# ADC.net
KiCad netlist of a schematic drawn in Altium Designer
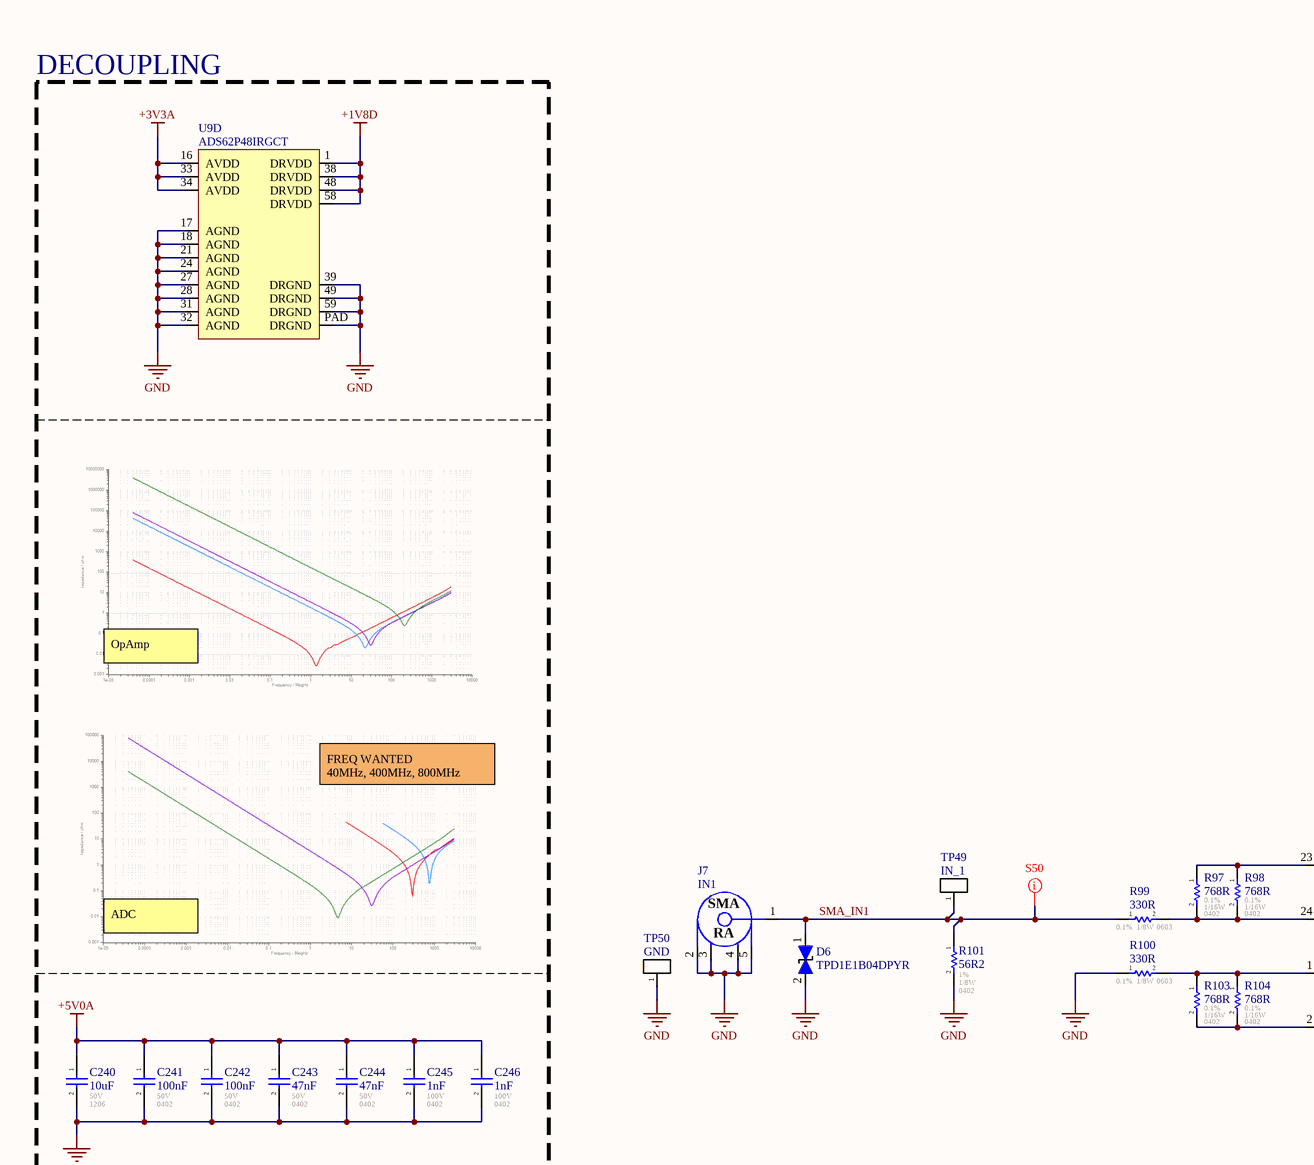
[diagram p0: ADC.SchDoc, top left]
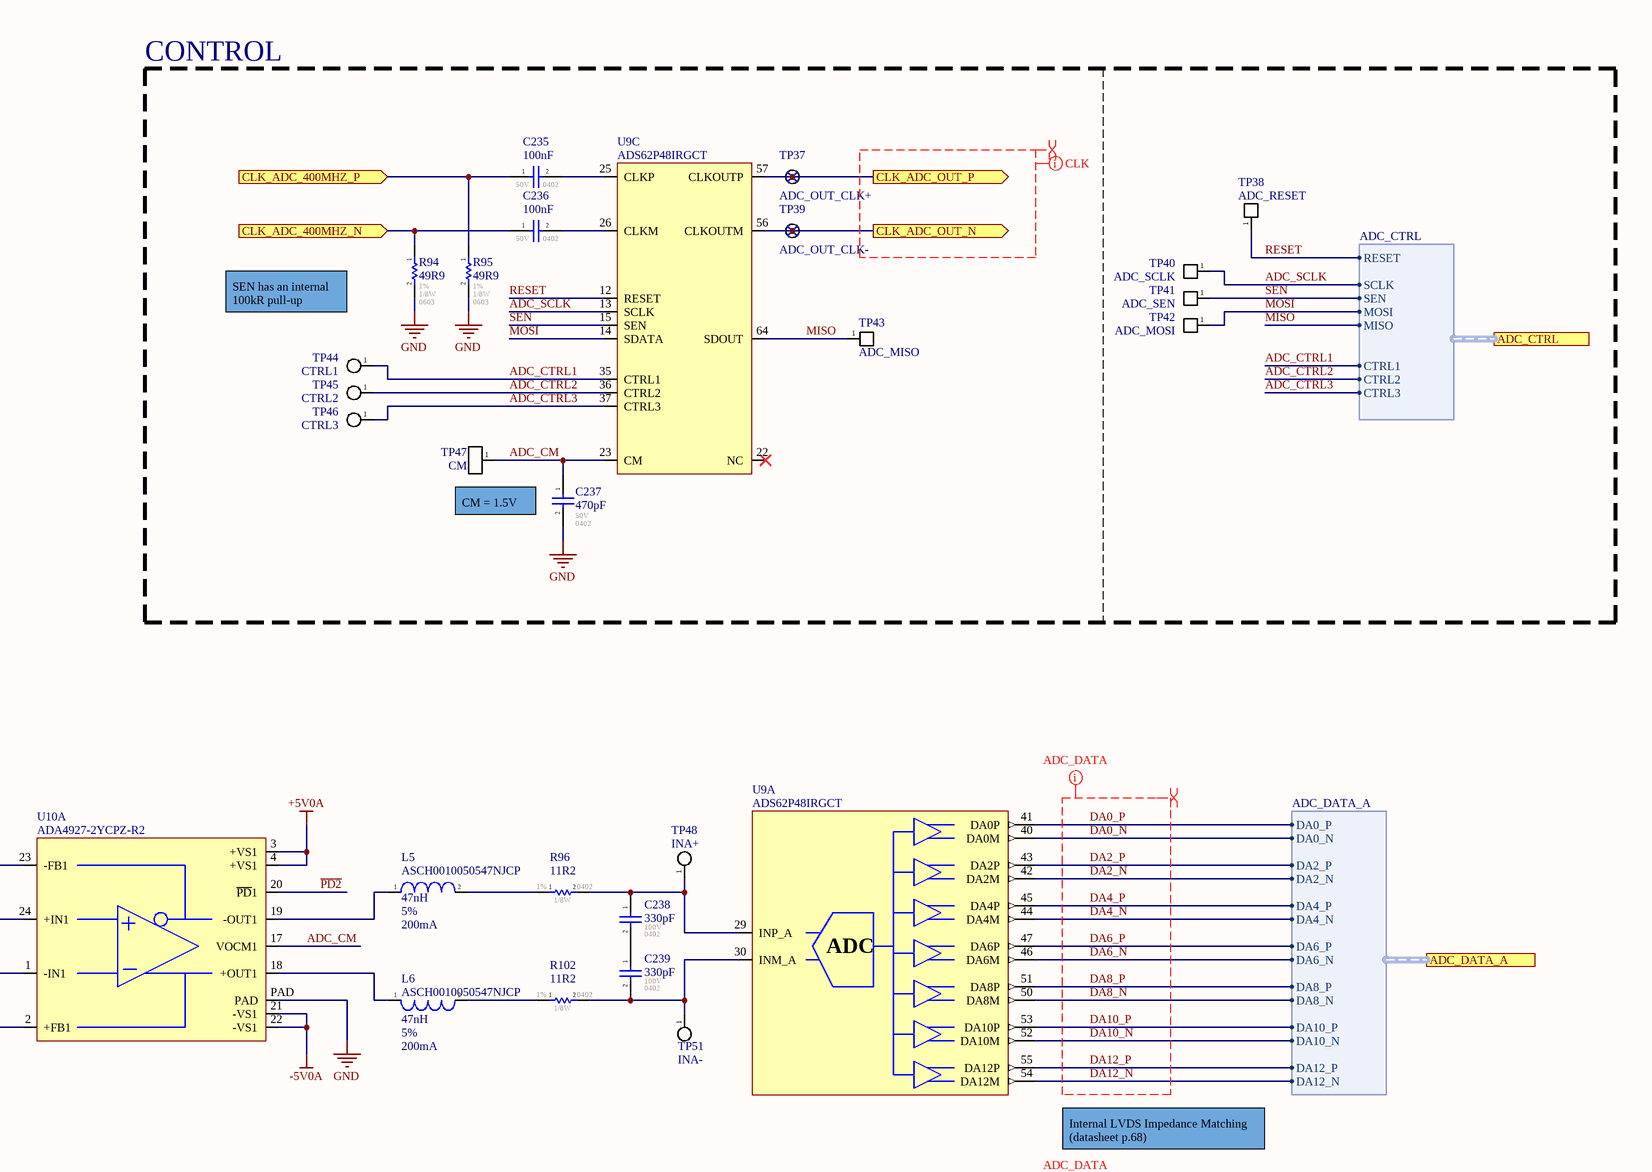
[diagram p1: ADC.SchDoc, top right]
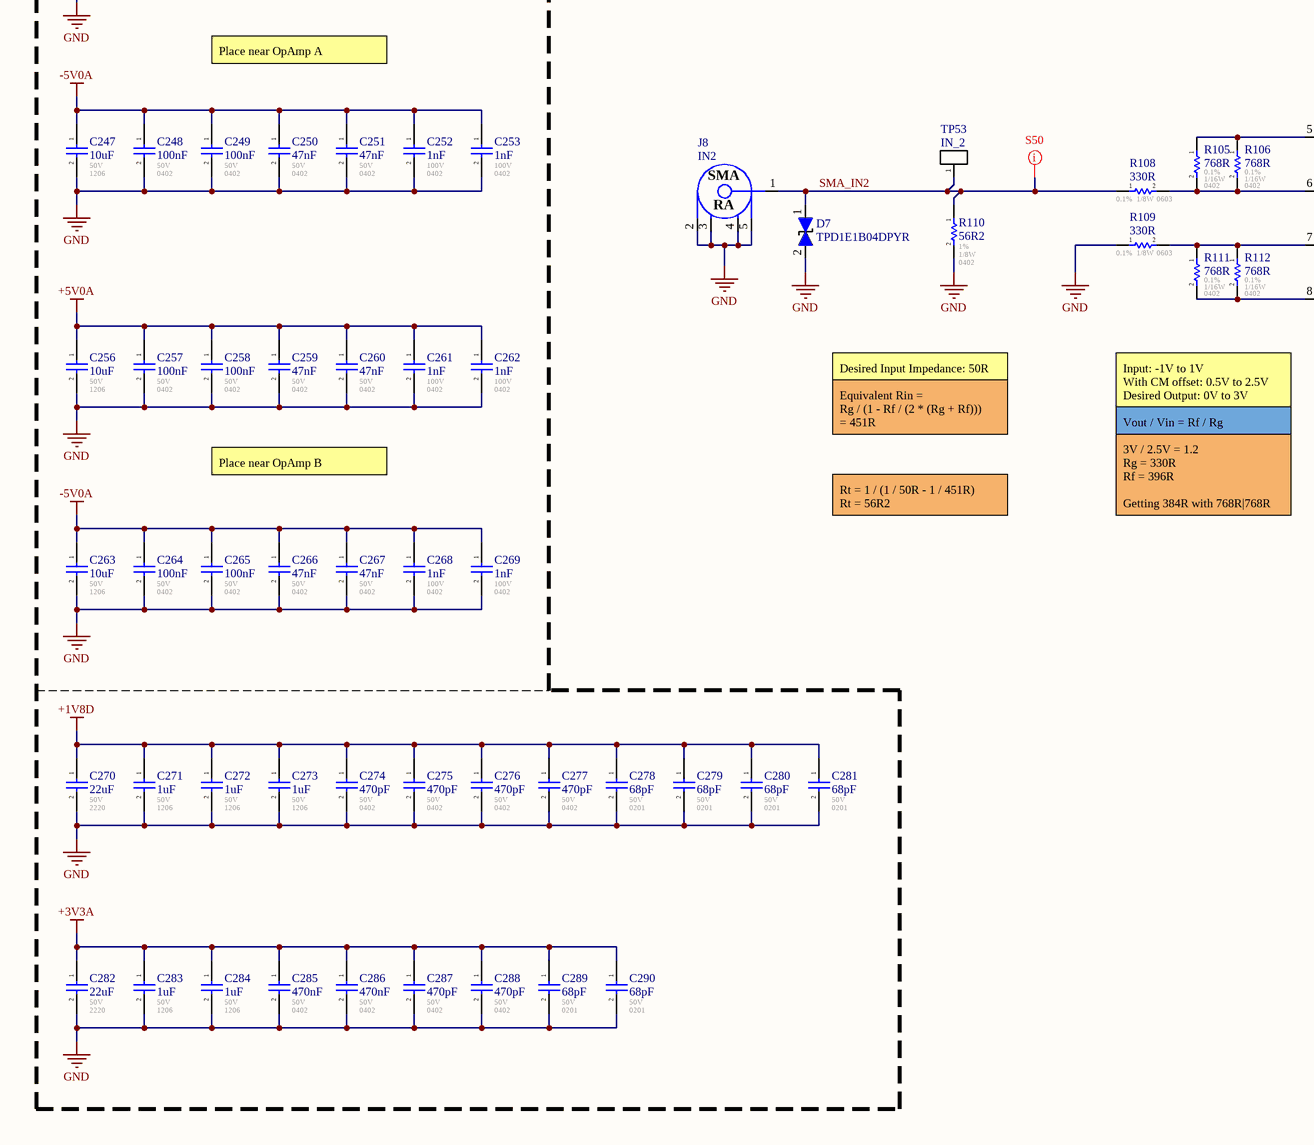
[diagram p2: ADC.SchDoc, bottom left]
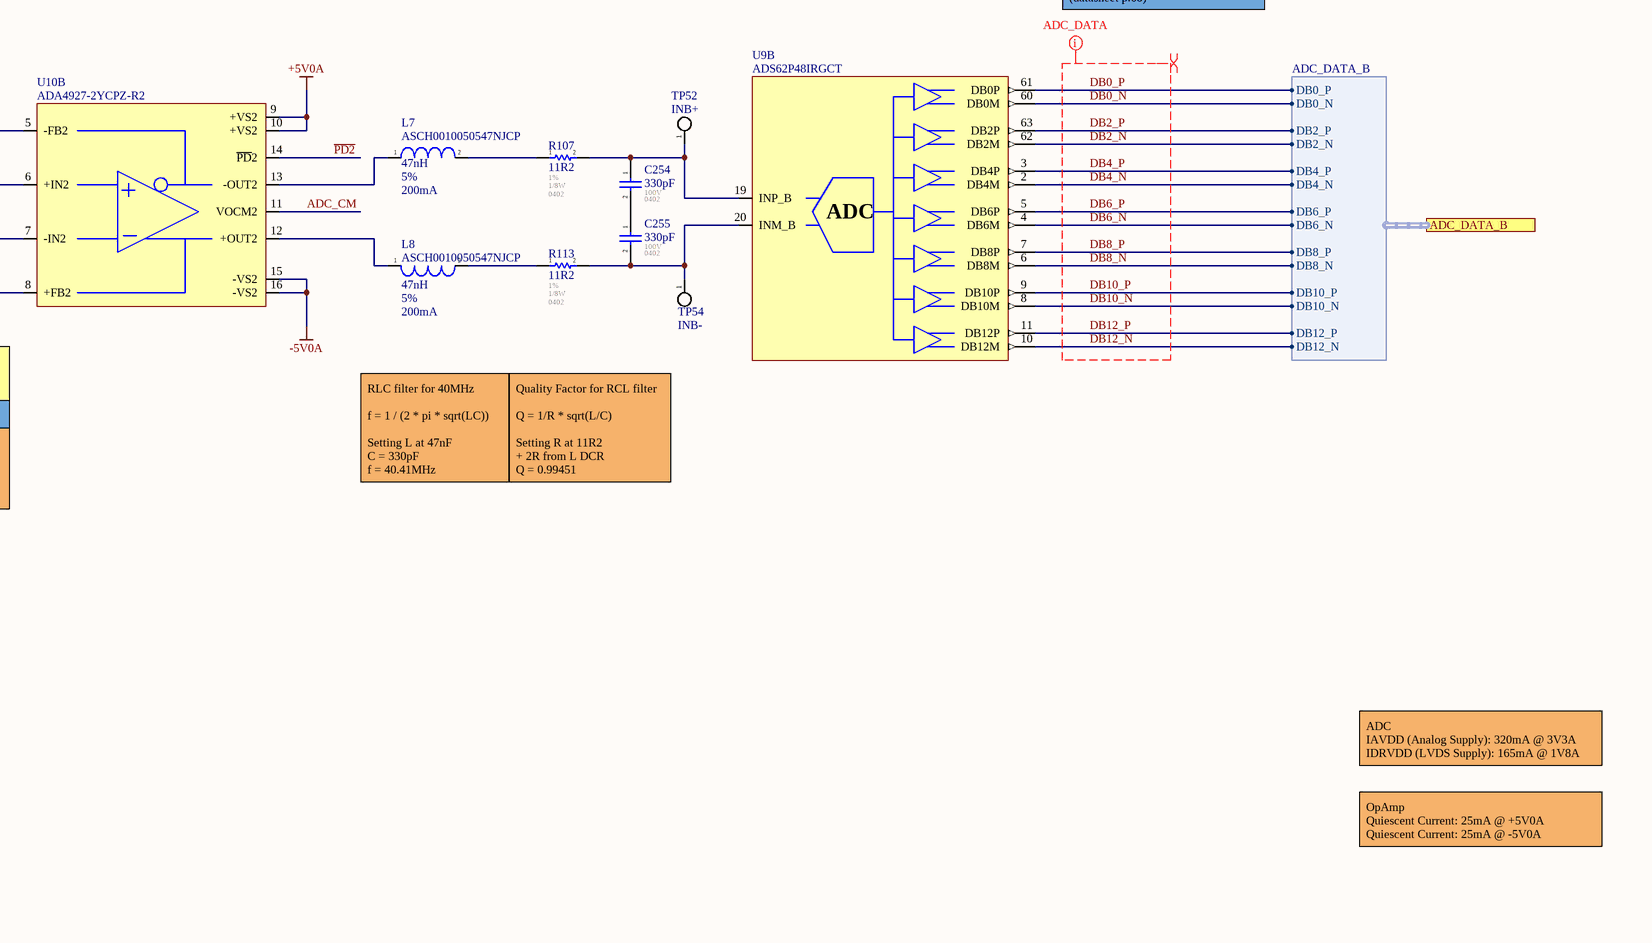
[diagram p3: ADC.SchDoc, bottom right]

(export (version "E")
  (design (tool "Eeschema 10.0.6"))
  (components
    (comp (ref "C235")
      (value "100nF")
      (footprint "0402")
      (description "GCM155R71H104KE02J\r\n0402 100nF 10% X7R Ceramic Capacitor")
      (fields
        (field (name "MFR") "Murata")
        (field (name "PART#") "GCM155R71H104KE02J")
        (field (name "VOLTAGE - RATED") "50V")
      )
      (libsource (lib "Symbols") (part "CAP_CER"))
    )
    (comp (ref "C236")
      (value "100nF")
      (footprint "0402")
      (description "GCM155R71H104KE02J\r\n0402 100nF 10% X7R Ceramic Capacitor")
      (fields
        (field (name "MFR") "Murata")
        (field (name "PART#") "GCM155R71H104KE02J")
        (field (name "VOLTAGE - RATED") "50V")
      )
      (libsource (lib "Symbols") (part "CAP_CER"))
    )
    (comp (ref "C237")
      (value "470pF")
      (footprint "0402")
      (description "GCM155R71H471KA37J\r\n0402 470pF 10% X7R Ceramic Capacitor")
      (fields
        (field (name "MFR") "Murata")
        (field (name "PART#") "GCM155R71H471KA37J")
        (field (name "VOLTAGE - RATED") "50V")
      )
      (libsource (lib "Symbols") (part "CAP_CER"))
    )
    (comp (ref "C238")
      (value "330pF")
      (footprint "0402")
      (description "GCM155R72A331KA37D\r\n0402 330pF 10% X7R Ceramic Capacitor")
      (fields
        (field (name "MFR") "Murata")
        (field (name "PART#") "GCM155R72A331KA37D")
        (field (name "VOLTAGE - RATED") "100V")
      )
      (libsource (lib "Symbols") (part "CAP_CER"))
    )
    (comp (ref "C239")
      (value "330pF")
      (footprint "0402")
      (description "GCM155R72A331KA37D\r\n0402 330pF 10% X7R Ceramic Capacitor")
      (fields
        (field (name "MFR") "Murata")
        (field (name "PART#") "GCM155R72A331KA37D")
        (field (name "VOLTAGE - RATED") "100V")
      )
      (libsource (lib "Symbols") (part "CAP_CER"))
    )
    (comp (ref "C240")
      (value "10uF")
      (footprint "1206")
      (description "GRT31CR61H106KE01L\r\n1206 10uF 10% X5R Ceramic Capacitor")
      (fields
        (field (name "MFR") "Murata")
        (field (name "VOLTAGE - RATED") "50V")
        (field (name "TOLERANCE") "10%")
      )
      (libsource (lib "Symbols") (part "CAP_CER"))
    )
    (comp (ref "C241")
      (value "100nF")
      (footprint "0402")
      (description "GCM155R71H104KE02J\r\n0402 100nF 10% X7R Ceramic Capacitor")
      (fields
        (field (name "MFR") "Murata")
        (field (name "PART#") "GCM155R71H104KE02J")
        (field (name "VOLTAGE - RATED") "50V")
      )
      (libsource (lib "Symbols") (part "CAP_CER"))
    )
    (comp (ref "C242")
      (value "100nF")
      (footprint "0402")
      (description "GCM155R71H104KE02J\r\n0402 100nF 10% X7R Ceramic Capacitor")
      (fields
        (field (name "MFR") "Murata")
        (field (name "PART#") "GCM155R71H104KE02J")
        (field (name "VOLTAGE - RATED") "50V")
      )
      (libsource (lib "Symbols") (part "CAP_CER"))
    )
    (comp (ref "C243")
      (value "47nF")
      (footprint "0402")
      (description "GCM155R71H473KE02J\r\n0402 47nF 10% X7R Ceramic Capacitor")
      (fields
        (field (name "MFR") "Murata")
        (field (name "PART#") "GCM155R71H473KE02J")
        (field (name "VOLTAGE - RATED") "50V")
      )
      (libsource (lib "Symbols") (part "CAP_CER"))
    )
    (comp (ref "C244")
      (value "47nF")
      (footprint "0402")
      (description "GCM155R71H473KE02J\r\n0402 47nF 10% X7R Ceramic Capacitor")
      (fields
        (field (name "MFR") "Murata")
        (field (name "PART#") "GCM155R71H473KE02J")
        (field (name "VOLTAGE - RATED") "50V")
      )
      (libsource (lib "Symbols") (part "CAP_CER"))
    )
    (comp (ref "C245")
      (value "1nF")
      (footprint "0402")
      (description "GCM155R72A102KA37D\r\n0402 1nF 10% X7R Ceramic Capacitor")
      (fields
        (field (name "MFR") "Murata")
        (field (name "PART#") "GCM155R72A102KA37D")
        (field (name "VOLTAGE - RATED") "100V")
      )
      (libsource (lib "Symbols") (part "CAP_CER"))
    )
    (comp (ref "C246")
      (value "1nF")
      (footprint "0402")
      (description "GCM155R72A102KA37D\r\n0402 1nF 10% X7R Ceramic Capacitor")
      (fields
        (field (name "MFR") "Murata")
        (field (name "PART#") "GCM155R72A102KA37D")
        (field (name "VOLTAGE - RATED") "100V")
      )
      (libsource (lib "Symbols") (part "CAP_CER"))
    )
    (comp (ref "C247")
      (value "10uF")
      (footprint "1206")
      (description "GRT31CR61H106KE01L\r\n1206 10uF 10% X5R Ceramic Capacitor")
      (fields
        (field (name "MFR") "Murata")
        (field (name "VOLTAGE - RATED") "50V")
        (field (name "TOLERANCE") "10%")
      )
      (libsource (lib "Symbols") (part "CAP_CER"))
    )
    (comp (ref "C248")
      (value "100nF")
      (footprint "0402")
      (description "GCM155R71H104KE02J\r\n0402 100nF 10% X7R Ceramic Capacitor")
      (fields
        (field (name "MFR") "Murata")
        (field (name "PART#") "GCM155R71H104KE02J")
        (field (name "VOLTAGE - RATED") "50V")
      )
      (libsource (lib "Symbols") (part "CAP_CER"))
    )
    (comp (ref "C249")
      (value "100nF")
      (footprint "0402")
      (description "GCM155R71H104KE02J\r\n0402 100nF 10% X7R Ceramic Capacitor")
      (fields
        (field (name "MFR") "Murata")
        (field (name "PART#") "GCM155R71H104KE02J")
        (field (name "VOLTAGE - RATED") "50V")
      )
      (libsource (lib "Symbols") (part "CAP_CER"))
    )
    (comp (ref "C250")
      (value "47nF")
      (footprint "0402")
      (description "GCM155R71H473KE02J\r\n0402 47nF 10% X7R Ceramic Capacitor")
      (fields
        (field (name "MFR") "Murata")
        (field (name "PART#") "GCM155R71H473KE02J")
        (field (name "VOLTAGE - RATED") "50V")
      )
      (libsource (lib "Symbols") (part "CAP_CER"))
    )
    (comp (ref "C251")
      (value "47nF")
      (footprint "0402")
      (description "GCM155R71H473KE02J\r\n0402 47nF 10% X7R Ceramic Capacitor")
      (fields
        (field (name "MFR") "Murata")
        (field (name "PART#") "GCM155R71H473KE02J")
        (field (name "VOLTAGE - RATED") "50V")
      )
      (libsource (lib "Symbols") (part "CAP_CER"))
    )
    (comp (ref "C252")
      (value "1nF")
      (footprint "0402")
      (description "GCM155R72A102KA37D\r\n0402 1nF 10% X7R Ceramic Capacitor")
      (fields
        (field (name "MFR") "Murata")
        (field (name "PART#") "GCM155R72A102KA37D")
        (field (name "VOLTAGE - RATED") "100V")
      )
      (libsource (lib "Symbols") (part "CAP_CER"))
    )
    (comp (ref "C253")
      (value "1nF")
      (footprint "0402")
      (description "GCM155R72A102KA37D\r\n0402 1nF 10% X7R Ceramic Capacitor")
      (fields
        (field (name "MFR") "Murata")
        (field (name "PART#") "GCM155R72A102KA37D")
        (field (name "VOLTAGE - RATED") "100V")
      )
      (libsource (lib "Symbols") (part "CAP_CER"))
    )
    (comp (ref "C254")
      (value "330pF")
      (footprint "0402")
      (description "GCM155R72A331KA37D\r\n0402 330pF 10% X7R Ceramic Capacitor")
      (fields
        (field (name "MFR") "Murata")
        (field (name "PART#") "GCM155R72A331KA37D")
        (field (name "VOLTAGE - RATED") "100V")
      )
      (libsource (lib "Symbols") (part "CAP_CER"))
    )
    (comp (ref "C255")
      (value "330pF")
      (footprint "0402")
      (description "GCM155R72A331KA37D\r\n0402 330pF 10% X7R Ceramic Capacitor")
      (fields
        (field (name "MFR") "Murata")
        (field (name "PART#") "GCM155R72A331KA37D")
        (field (name "VOLTAGE - RATED") "100V")
      )
      (libsource (lib "Symbols") (part "CAP_CER"))
    )
    (comp (ref "C256")
      (value "10uF")
      (footprint "1206")
      (description "GRT31CR61H106KE01L\r\n1206 10uF 10% X5R Ceramic Capacitor")
      (fields
        (field (name "MFR") "Murata")
        (field (name "VOLTAGE - RATED") "50V")
        (field (name "TOLERANCE") "10%")
      )
      (libsource (lib "Symbols") (part "CAP_CER"))
    )
    (comp (ref "C257")
      (value "100nF")
      (footprint "0402")
      (description "GCM155R71H104KE02J\r\n0402 100nF 10% X7R Ceramic Capacitor")
      (fields
        (field (name "MFR") "Murata")
        (field (name "PART#") "GCM155R71H104KE02J")
        (field (name "VOLTAGE - RATED") "50V")
      )
      (libsource (lib "Symbols") (part "CAP_CER"))
    )
    (comp (ref "C258")
      (value "100nF")
      (footprint "0402")
      (description "GCM155R71H104KE02J\r\n0402 100nF 10% X7R Ceramic Capacitor")
      (fields
        (field (name "MFR") "Murata")
        (field (name "PART#") "GCM155R71H104KE02J")
        (field (name "VOLTAGE - RATED") "50V")
      )
      (libsource (lib "Symbols") (part "CAP_CER"))
    )
    (comp (ref "C259")
      (value "47nF")
      (footprint "0402")
      (description "GCM155R71H473KE02J\r\n0402 47nF 10% X7R Ceramic Capacitor")
      (fields
        (field (name "MFR") "Murata")
        (field (name "PART#") "GCM155R71H473KE02J")
        (field (name "VOLTAGE - RATED") "50V")
      )
      (libsource (lib "Symbols") (part "CAP_CER"))
    )
    (comp (ref "C260")
      (value "47nF")
      (footprint "0402")
      (description "GCM155R71H473KE02J\r\n0402 47nF 10% X7R Ceramic Capacitor")
      (fields
        (field (name "MFR") "Murata")
        (field (name "PART#") "GCM155R71H473KE02J")
        (field (name "VOLTAGE - RATED") "50V")
      )
      (libsource (lib "Symbols") (part "CAP_CER"))
    )
    (comp (ref "C261")
      (value "1nF")
      (footprint "0402")
      (description "GCM155R72A102KA37D\r\n0402 1nF 10% X7R Ceramic Capacitor")
      (fields
        (field (name "MFR") "Murata")
        (field (name "PART#") "GCM155R72A102KA37D")
        (field (name "VOLTAGE - RATED") "100V")
      )
      (libsource (lib "Symbols") (part "CAP_CER"))
    )
    (comp (ref "C262")
      (value "1nF")
      (footprint "0402")
      (description "GCM155R72A102KA37D\r\n0402 1nF 10% X7R Ceramic Capacitor")
      (fields
        (field (name "MFR") "Murata")
        (field (name "PART#") "GCM155R72A102KA37D")
        (field (name "VOLTAGE - RATED") "100V")
      )
      (libsource (lib "Symbols") (part "CAP_CER"))
    )
    (comp (ref "C263")
      (value "10uF")
      (footprint "1206")
      (description "GRT31CR61H106KE01L\r\n1206 10uF 10% X5R Ceramic Capacitor")
      (fields
        (field (name "MFR") "Murata")
        (field (name "VOLTAGE - RATED") "50V")
        (field (name "TOLERANCE") "10%")
      )
      (libsource (lib "Symbols") (part "CAP_CER"))
    )
    (comp (ref "C264")
      (value "100nF")
      (footprint "0402")
      (description "GCM155R71H104KE02J\r\n0402 100nF 10% X7R Ceramic Capacitor")
      (fields
        (field (name "MFR") "Murata")
        (field (name "PART#") "GCM155R71H104KE02J")
        (field (name "VOLTAGE - RATED") "50V")
      )
      (libsource (lib "Symbols") (part "CAP_CER"))
    )
    (comp (ref "C265")
      (value "100nF")
      (footprint "0402")
      (description "GCM155R71H104KE02J\r\n0402 100nF 10% X7R Ceramic Capacitor")
      (fields
        (field (name "MFR") "Murata")
        (field (name "PART#") "GCM155R71H104KE02J")
        (field (name "VOLTAGE - RATED") "50V")
      )
      (libsource (lib "Symbols") (part "CAP_CER"))
    )
    (comp (ref "C266")
      (value "47nF")
      (footprint "0402")
      (description "GCM155R71H473KE02J\r\n0402 47nF 10% X7R Ceramic Capacitor")
      (fields
        (field (name "MFR") "Murata")
        (field (name "PART#") "GCM155R71H473KE02J")
        (field (name "VOLTAGE - RATED") "50V")
      )
      (libsource (lib "Symbols") (part "CAP_CER"))
    )
    (comp (ref "C267")
      (value "47nF")
      (footprint "0402")
      (description "GCM155R71H473KE02J\r\n0402 47nF 10% X7R Ceramic Capacitor")
      (fields
        (field (name "MFR") "Murata")
        (field (name "PART#") "GCM155R71H473KE02J")
        (field (name "VOLTAGE - RATED") "50V")
      )
      (libsource (lib "Symbols") (part "CAP_CER"))
    )
    (comp (ref "C268")
      (value "1nF")
      (footprint "0402")
      (description "GCM155R72A102KA37D\r\n0402 1nF 10% X7R Ceramic Capacitor")
      (fields
        (field (name "MFR") "Murata")
        (field (name "PART#") "GCM155R72A102KA37D")
        (field (name "VOLTAGE - RATED") "100V")
      )
      (libsource (lib "Symbols") (part "CAP_CER"))
    )
    (comp (ref "C269")
      (value "1nF")
      (footprint "0402")
      (description "GCM155R72A102KA37D\r\n0402 1nF 10% X7R Ceramic Capacitor")
      (fields
        (field (name "MFR") "Murata")
        (field (name "PART#") "GCM155R72A102KA37D")
        (field (name "VOLTAGE - RATED") "100V")
      )
      (libsource (lib "Symbols") (part "CAP_CER"))
    )
    (comp (ref "C270")
      (value "22uF")
      (footprint "2220")
      (description "CGA9P3X7R1H226M250KB\r\n2220 22uF 20% X7R Ceramic Capacitor")
      (fields
        (field (name "MFR") "TDK")
        (field (name "VOLTAGE - RATED") "50V")
        (field (name "TOLERANCE") "20%")
      )
      (libsource (lib "Symbols") (part "CAP_CER"))
    )
    (comp (ref "C271")
      (value "1uF")
      (footprint "1206")
      (description "GCJ31CR71H105KA12L\r\n1206 1uF 10% X7R Ceramic Capacitor")
      (fields
        (field (name "MFR") "Murata")
        (field (name "PART#") "GCJ31CR71H105KA12L")
        (field (name "VOLTAGE - RATED") "50V")
      )
      (libsource (lib "Symbols") (part "CAP_CER"))
    )
    (comp (ref "C272")
      (value "1uF")
      (footprint "1206")
      (description "GCJ31CR71H105KA12L\r\n1206 1uF 10% X7R Ceramic Capacitor")
      (fields
        (field (name "MFR") "Murata")
        (field (name "PART#") "GCJ31CR71H105KA12L")
        (field (name "VOLTAGE - RATED") "50V")
      )
      (libsource (lib "Symbols") (part "CAP_CER"))
    )
    (comp (ref "C273")
      (value "1uF")
      (footprint "1206")
      (description "GCJ31CR71H105KA12L\r\n1206 1uF 10% X7R Ceramic Capacitor")
      (fields
        (field (name "MFR") "Murata")
        (field (name "PART#") "GCJ31CR71H105KA12L")
        (field (name "VOLTAGE - RATED") "50V")
      )
      (libsource (lib "Symbols") (part "CAP_CER"))
    )
    (comp (ref "C274")
      (value "470pF")
      (footprint "0402")
      (description "GCM155R71H471KA37J\r\n0402 470pF 10% X7R Ceramic Capacitor")
      (fields
        (field (name "MFR") "Murata")
        (field (name "PART#") "GCM155R71H471KA37J")
        (field (name "VOLTAGE - RATED") "50V")
      )
      (libsource (lib "Symbols") (part "CAP_CER"))
    )
    (comp (ref "C275")
      (value "470pF")
      (footprint "0402")
      (description "GCM155R71H471KA37J\r\n0402 470pF 10% X7R Ceramic Capacitor")
      (fields
        (field (name "MFR") "Murata")
        (field (name "PART#") "GCM155R71H471KA37J")
        (field (name "VOLTAGE - RATED") "50V")
      )
      (libsource (lib "Symbols") (part "CAP_CER"))
    )
    (comp (ref "C276")
      (value "470pF")
      (footprint "0402")
      (description "GCM155R71H471KA37J\r\n0402 470pF 10% X7R Ceramic Capacitor")
      (fields
        (field (name "MFR") "Murata")
        (field (name "PART#") "GCM155R71H471KA37J")
        (field (name "VOLTAGE - RATED") "50V")
      )
      (libsource (lib "Symbols") (part "CAP_CER"))
    )
    (comp (ref "C277")
      (value "470pF")
      (footprint "0402")
      (description "GCM155R71H471KA37J\r\n0402 470pF 10% X7R Ceramic Capacitor")
      (fields
        (field (name "MFR") "Murata")
        (field (name "PART#") "GCM155R71H471KA37J")
        (field (name "VOLTAGE - RATED") "50V")
      )
      (libsource (lib "Symbols") (part "CAP_CER"))
    )
    (comp (ref "C278")
      (value "68pF")
      (footprint "0201")
      (description "0201 68pF 5% C0G 50V Ceramic Capacitor\r\nCGA1A2C0G1H680J030BA")
      (fields
        (field (name "MFR") "TDK")
        (field (name "PART#") "CGA1A2C0G1H680J030BA")
        (field (name "VOLTAGE - RATED") "50V")
      )
      (libsource (lib "Symbols") (part "CAP_CER"))
    )
    (comp (ref "C279")
      (value "68pF")
      (footprint "0201")
      (description "0201 68pF 5% C0G 50V Ceramic Capacitor\r\nCGA1A2C0G1H680J030BA")
      (fields
        (field (name "MFR") "TDK")
        (field (name "PART#") "CGA1A2C0G1H680J030BA")
        (field (name "VOLTAGE - RATED") "50V")
      )
      (libsource (lib "Symbols") (part "CAP_CER"))
    )
    (comp (ref "C280")
      (value "68pF")
      (footprint "0201")
      (description "0201 68pF 5% C0G 50V Ceramic Capacitor\r\nCGA1A2C0G1H680J030BA")
      (fields
        (field (name "MFR") "TDK")
        (field (name "PART#") "CGA1A2C0G1H680J030BA")
        (field (name "VOLTAGE - RATED") "50V")
      )
      (libsource (lib "Symbols") (part "CAP_CER"))
    )
    (comp (ref "C281")
      (value "68pF")
      (footprint "0201")
      (description "0201 68pF 5% C0G 50V Ceramic Capacitor\r\nCGA1A2C0G1H680J030BA")
      (fields
        (field (name "MFR") "TDK")
        (field (name "PART#") "CGA1A2C0G1H680J030BA")
        (field (name "VOLTAGE - RATED") "50V")
      )
      (libsource (lib "Symbols") (part "CAP_CER"))
    )
    (comp (ref "C282")
      (value "22uF")
      (footprint "2220")
      (description "CGA9P3X7R1H226M250KB\r\n2220 22uF 20% X7R Ceramic Capacitor")
      (fields
        (field (name "MFR") "TDK")
        (field (name "VOLTAGE - RATED") "50V")
        (field (name "TOLERANCE") "20%")
      )
      (libsource (lib "Symbols") (part "CAP_CER"))
    )
    (comp (ref "C283")
      (value "1uF")
      (footprint "1206")
      (description "GCJ31CR71H105KA12L\r\n1206 1uF 10% X7R Ceramic Capacitor")
      (fields
        (field (name "MFR") "Murata")
        (field (name "PART#") "GCJ31CR71H105KA12L")
        (field (name "VOLTAGE - RATED") "50V")
      )
      (libsource (lib "Symbols") (part "CAP_CER"))
    )
    (comp (ref "C284")
      (value "1uF")
      (footprint "1206")
      (description "GCJ31CR71H105KA12L\r\n1206 1uF 10% X7R Ceramic Capacitor")
      (fields
        (field (name "MFR") "Murata")
        (field (name "PART#") "GCJ31CR71H105KA12L")
        (field (name "VOLTAGE - RATED") "50V")
      )
      (libsource (lib "Symbols") (part "CAP_CER"))
    )
    (comp (ref "C285")
      (value "470nF")
      (footprint "0402")
      (description "CGA3E3X7R1H474K080AB\r\n0603 470nF 10% X7R Ceramic Capacitor")
      (fields
        (field (name "MFR") "TDK")
        (field (name "PART#") "CGA3E3X7R1H474K080AB")
        (field (name "VOLTAGE - RATED") "50V")
      )
      (libsource (lib "Symbols") (part "CAP_CER"))
    )
    (comp (ref "C286")
      (value "470nF")
      (footprint "0402")
      (description "CGA3E3X7R1H474K080AB\r\n0603 470nF 10% X7R Ceramic Capacitor")
      (fields
        (field (name "MFR") "TDK")
        (field (name "PART#") "CGA3E3X7R1H474K080AB")
        (field (name "VOLTAGE - RATED") "50V")
      )
      (libsource (lib "Symbols") (part "CAP_CER"))
    )
    (comp (ref "C287")
      (value "470pF")
      (footprint "0402")
      (description "GCM155R71H471KA37J\r\n0402 470pF 10% X7R Ceramic Capacitor")
      (fields
        (field (name "MFR") "Murata")
        (field (name "PART#") "GCM155R71H471KA37J")
        (field (name "VOLTAGE - RATED") "50V")
      )
      (libsource (lib "Symbols") (part "CAP_CER"))
    )
    (comp (ref "C288")
      (value "470pF")
      (footprint "0402")
      (description "GCM155R71H471KA37J\r\n0402 470pF 10% X7R Ceramic Capacitor")
      (fields
        (field (name "MFR") "Murata")
        (field (name "PART#") "GCM155R71H471KA37J")
        (field (name "VOLTAGE - RATED") "50V")
      )
      (libsource (lib "Symbols") (part "CAP_CER"))
    )
    (comp (ref "C289")
      (value "68pF")
      (footprint "0201")
      (description "0201 68pF 5% C0G 50V Ceramic Capacitor\r\nCGA1A2C0G1H680J030BA")
      (fields
        (field (name "MFR") "TDK")
        (field (name "PART#") "CGA1A2C0G1H680J030BA")
        (field (name "VOLTAGE - RATED") "50V")
      )
      (libsource (lib "Symbols") (part "CAP_CER"))
    )
    (comp (ref "C290")
      (value "68pF")
      (footprint "0201")
      (description "0201 68pF 5% C0G 50V Ceramic Capacitor\r\nCGA1A2C0G1H680J030BA")
      (fields
        (field (name "MFR") "TDK")
        (field (name "PART#") "CGA1A2C0G1H680J030BA")
        (field (name "VOLTAGE - RATED") "50V")
      )
      (libsource (lib "Symbols") (part "CAP_CER"))
    )
    (comp (ref "D6")
      (value "TPD1E1B04DPYR")
      (footprint "TVS_DATA_TPD1E1B04DPYR")
      (description "TVS - TVS DIODE 3.6V 8.5V - 0402")
      (fields
        (field (name "CREATEDBY/DATE") "Keven Deslandes - 2018/10/19")
        (field (name "VERIFIEDBY") "Caroline Paulin - 28 janv 2019")
      )
      (libsource (lib "S7CAS_LIB2023") (part "TVS_DATA_TPD1E1B04DPYR"))
    )
    (comp (ref "D7")
      (value "TPD1E1B04DPYR")
      (footprint "TVS_DATA_TPD1E1B04DPYR")
      (description "TVS - TVS DIODE 3.6V 8.5V - 0402")
      (fields
        (field (name "CREATEDBY/DATE") "Keven Deslandes - 2018/10/19")
        (field (name "VERIFIEDBY") "Caroline Paulin - 28 janv 2019")
      )
      (libsource (lib "S7CAS_LIB2023") (part "TVS_DATA_TPD1E1B04DPYR"))
    )
    (comp (ref "J7")
      (value "IN1")
      (footprint "CONN_SMA_5-1814400-1")
      (description "5-1814400-1\r\nCONN -  SMA JACK R/A 50 OHM - TH")
      (fields
        (field (name "MFG") "TE Connectivity AMP Connectors")
        (field (name "MFG PART NUMBER") "5-1814400-1")
        (field (name "CREATEDBY") "Jonathan Bouchard")
      )
      (libsource (lib "S7CAS_LIB2023") (part "CONN_SMA_5-1814400-1"))
    )
    (comp (ref "J8")
      (value "IN2")
      (footprint "CONN_SMA_5-1814400-1")
      (description "5-1814400-1\r\nCONN -  SMA JACK R/A 50 OHM - TH")
      (fields
        (field (name "MFG") "TE Connectivity AMP Connectors")
        (field (name "MFG PART NUMBER") "5-1814400-1")
        (field (name "CREATEDBY") "Jonathan Bouchard")
      )
      (libsource (lib "S7CAS_LIB2023") (part "CONN_SMA_5-1814400-1"))
    )
    (comp (ref "L5")
      (value "ASCH0010050547NJCP")
      (footprint "IND_0402")
      (description "Generic Inductor")
      (fields
        (field (name "INDUCTANCE") "47nH")
        (field (name "TOLERANCE") "5%")
        (field (name "CURRENT RATING") "200mA")
      )
      (libsource (lib "Symbols") (part "INDUCTOR"))
    )
    (comp (ref "L6")
      (value "ASCH0010050547NJCP")
      (footprint "IND_0402")
      (description "Generic Inductor")
      (fields
        (field (name "INDUCTANCE") "47nH")
        (field (name "TOLERANCE") "5%")
        (field (name "CURRENT RATING") "200mA")
      )
      (libsource (lib "Symbols") (part "INDUCTOR"))
    )
    (comp (ref "L7")
      (value "ASCH0010050547NJCP")
      (footprint "IND_0402")
      (description "Generic Inductor")
      (fields
        (field (name "INDUCTANCE") "47nH")
        (field (name "TOLERANCE") "5%")
        (field (name "CURRENT RATING") "200mA")
      )
      (libsource (lib "Symbols") (part "INDUCTOR"))
    )
    (comp (ref "L8")
      (value "ASCH0010050547NJCP")
      (footprint "IND_0402")
      (description "Generic Inductor")
      (fields
        (field (name "INDUCTANCE") "47nH")
        (field (name "TOLERANCE") "5%")
        (field (name "CURRENT RATING") "200mA")
      )
      (libsource (lib "Symbols") (part "INDUCTOR"))
    )
    (comp (ref "R94")
      (value "49R9")
      (footprint "RES_0603")
      (fields
        (field (name "TOLERANCE") "1%")
        (field (name "POWER") "1/8W")
        (field (name "PACKAGE / CASE") "0603")
      )
      (libsource (lib "Symbols") (part "RESISTOR"))
    )
    (comp (ref "R95")
      (value "49R9")
      (footprint "RES_0603")
      (fields
        (field (name "TOLERANCE") "1%")
        (field (name "POWER") "1/8W")
        (field (name "PACKAGE / CASE") "0603")
      )
      (libsource (lib "Symbols") (part "RESISTOR"))
    )
    (comp (ref "R96")
      (value "11R2")
      (footprint "RES_0402")
      (fields
        (field (name "TOLERANCE") "1%")
        (field (name "POWER") "1/8W")
        (field (name "PACKAGE / CASE") "0402")
      )
      (libsource (lib "Symbols") (part "RESISTOR"))
    )
    (comp (ref "R97")
      (value "768R")
      (footprint "RES_0402")
      (fields
        (field (name "TOLERANCE") "0.1%")
        (field (name "POWER") "1/16W")
        (field (name "PACKAGE / CASE") "0402")
      )
      (libsource (lib "Symbols") (part "RESISTOR"))
    )
    (comp (ref "R98")
      (value "768R")
      (footprint "RES_0402")
      (fields
        (field (name "TOLERANCE") "0.1%")
        (field (name "POWER") "1/16W")
        (field (name "PACKAGE / CASE") "0402")
      )
      (libsource (lib "Symbols") (part "RESISTOR"))
    )
    (comp (ref "R99")
      (value "330R")
      (footprint "RES_0603")
      (description "1M 0603 1% 1/16W Resistor")
      (fields
        (field (name "TOLERANCE") "0.1%")
        (field (name "POWER") "1/8W")
        (field (name "PACKAGE / CASE") "0603")
      )
      (libsource (lib "Symbols") (part "RESISTOR"))
    )
    (comp (ref "R100")
      (value "330R")
      (footprint "RES_0603")
      (description "1M 0603 1% 1/16W Resistor")
      (fields
        (field (name "TOLERANCE") "0.1%")
        (field (name "POWER") "1/8W")
        (field (name "PACKAGE / CASE") "0603")
      )
      (libsource (lib "Symbols") (part "RESISTOR"))
    )
    (comp (ref "R101")
      (value "56R2")
      (footprint "RES_0402")
      (fields
        (field (name "TOLERANCE") "1%")
        (field (name "POWER") "1/8W")
        (field (name "PACKAGE / CASE") "0402")
      )
      (libsource (lib "Symbols") (part "RESISTOR"))
    )
    (comp (ref "R102")
      (value "11R2")
      (footprint "RES_0402")
      (fields
        (field (name "TOLERANCE") "1%")
        (field (name "POWER") "1/8W")
        (field (name "PACKAGE / CASE") "0402")
      )
      (libsource (lib "Symbols") (part "RESISTOR"))
    )
    (comp (ref "R103")
      (value "768R")
      (footprint "RES_0402")
      (fields
        (field (name "TOLERANCE") "0.1%")
        (field (name "POWER") "1/16W")
        (field (name "PACKAGE / CASE") "0402")
      )
      (libsource (lib "Symbols") (part "RESISTOR"))
    )
    (comp (ref "R104")
      (value "768R")
      (footprint "RES_0402")
      (fields
        (field (name "TOLERANCE") "0.1%")
        (field (name "POWER") "1/16W")
        (field (name "PACKAGE / CASE") "0402")
      )
      (libsource (lib "Symbols") (part "RESISTOR"))
    )
    (comp (ref "R105")
      (value "768R")
      (footprint "RES_0402")
      (fields
        (field (name "TOLERANCE") "0.1%")
        (field (name "POWER") "1/16W")
        (field (name "PACKAGE / CASE") "0402")
      )
      (libsource (lib "Symbols") (part "RESISTOR"))
    )
    (comp (ref "R106")
      (value "768R")
      (footprint "RES_0402")
      (fields
        (field (name "TOLERANCE") "0.1%")
        (field (name "POWER") "1/16W")
        (field (name "PACKAGE / CASE") "0402")
      )
      (libsource (lib "Symbols") (part "RESISTOR"))
    )
    (comp (ref "R107")
      (value "11R2")
      (footprint "RES_0402")
      (fields
        (field (name "TOLERANCE") "1%")
        (field (name "POWER") "1/8W")
        (field (name "PACKAGE / CASE") "0402")
      )
      (libsource (lib "Symbols") (part "RESISTOR"))
    )
    (comp (ref "R108")
      (value "330R")
      (footprint "RES_0603")
      (description "1M 0603 1% 1/16W Resistor")
      (fields
        (field (name "TOLERANCE") "0.1%")
        (field (name "POWER") "1/8W")
        (field (name "PACKAGE / CASE") "0603")
      )
      (libsource (lib "Symbols") (part "RESISTOR"))
    )
    (comp (ref "R109")
      (value "330R")
      (footprint "RES_0603")
      (description "1M 0603 1% 1/16W Resistor")
      (fields
        (field (name "TOLERANCE") "0.1%")
        (field (name "POWER") "1/8W")
        (field (name "PACKAGE / CASE") "0603")
      )
      (libsource (lib "Symbols") (part "RESISTOR"))
    )
    (comp (ref "R110")
      (value "56R2")
      (footprint "RES_0402")
      (fields
        (field (name "TOLERANCE") "1%")
        (field (name "POWER") "1/8W")
        (field (name "PACKAGE / CASE") "0402")
      )
      (libsource (lib "Symbols") (part "RESISTOR"))
    )
    (comp (ref "R111")
      (value "768R")
      (footprint "RES_0402")
      (fields
        (field (name "TOLERANCE") "0.1%")
        (field (name "POWER") "1/16W")
        (field (name "PACKAGE / CASE") "0402")
      )
      (libsource (lib "Symbols") (part "RESISTOR"))
    )
    (comp (ref "R112")
      (value "768R")
      (footprint "RES_0402")
      (fields
        (field (name "TOLERANCE") "0.1%")
        (field (name "POWER") "1/16W")
        (field (name "PACKAGE / CASE") "0402")
      )
      (libsource (lib "Symbols") (part "RESISTOR"))
    )
    (comp (ref "R113")
      (value "11R2")
      (footprint "RES_0402")
      (fields
        (field (name "TOLERANCE") "1%")
        (field (name "POWER") "1/8W")
        (field (name "PACKAGE / CASE") "0402")
      )
      (libsource (lib "Symbols") (part "RESISTOR"))
    )
    (comp (ref "TP37")
      (value "ADC_OUT_CLK+")
      (footprint "TP_PAD_TINY")
      (description "Test Point")
      (libsource (lib "Symbols") (part "TESTPOINT_PAD_TINY"))
    )
    (comp (ref "TP38")
      (value "ADC_RESET")
      (footprint "TP_PAD")
      (description "Test Point")
      (libsource (lib "Symbols") (part "TESTPOINT_PAD"))
    )
    (comp (ref "TP39")
      (value "ADC_OUT_CLK-")
      (footprint "TP_PAD_TINY")
      (description "Test Point")
      (libsource (lib "Symbols") (part "TESTPOINT_PAD_TINY"))
    )
    (comp (ref "TP40")
      (value "ADC_SCLK")
      (footprint "TP_PAD")
      (description "Test Point")
      (libsource (lib "Symbols") (part "TESTPOINT_PAD"))
    )
    (comp (ref "TP41")
      (value "ADC_SEN")
      (footprint "TP_PAD")
      (description "Test Point")
      (libsource (lib "Symbols") (part "TESTPOINT_PAD"))
    )
    (comp (ref "TP42")
      (value "ADC_MOSI")
      (footprint "TP_PAD")
      (description "Test Point")
      (libsource (lib "Symbols") (part "TESTPOINT_PAD"))
    )
    (comp (ref "TP43")
      (value "ADC_MISO")
      (footprint "TP_PAD")
      (description "Test Point")
      (libsource (lib "Symbols") (part "TESTPOINT_PAD"))
    )
    (comp (ref "TP44")
      (value "CTRL1")
      (footprint "TP_PAD_SMALL")
      (description "Test Point")
      (libsource (lib "Symbols") (part "TESTPOINT_PAD_SMALL"))
    )
    (comp (ref "TP45")
      (value "CTRL2")
      (footprint "TP_PAD_SMALL")
      (description "Test Point")
      (libsource (lib "Symbols") (part "TESTPOINT_PAD_SMALL"))
    )
    (comp (ref "TP46")
      (value "CTRL3")
      (footprint "TP_PAD_SMALL")
      (description "Test Point")
      (libsource (lib "Symbols") (part "TESTPOINT_PAD_SMALL"))
    )
    (comp (ref "TP47")
      (value "CM")
      (footprint "TP_HOLE")
      (description "Test Point")
      (libsource (lib "Symbols") (part "TESTPOINT"))
    )
    (comp (ref "TP48")
      (value "INA+")
      (footprint "TP_PAD_SMALL")
      (description "Test Point")
      (libsource (lib "Symbols") (part "TESTPOINT_PAD_SMALL"))
    )
    (comp (ref "TP49")
      (value "IN_1")
      (footprint "TP_HOLE")
      (description "Test Point")
      (libsource (lib "Symbols") (part "TESTPOINT"))
    )
    (comp (ref "TP50")
      (value "GND")
      (footprint "TP_HOLE")
      (description "Test Point")
      (libsource (lib "Symbols") (part "TESTPOINT"))
    )
    (comp (ref "TP51")
      (value "INA-")
      (footprint "TP_PAD_SMALL")
      (description "Test Point")
      (libsource (lib "Symbols") (part "TESTPOINT_PAD_SMALL"))
    )
    (comp (ref "TP52")
      (value "INB+")
      (footprint "TP_PAD_SMALL")
      (description "Test Point")
      (libsource (lib "Symbols") (part "TESTPOINT_PAD_SMALL"))
    )
    (comp (ref "TP53")
      (value "IN_2")
      (footprint "TP_HOLE")
      (description "Test Point")
      (libsource (lib "Symbols") (part "TESTPOINT"))
    )
    (comp (ref "TP54")
      (value "INB-")
      (footprint "TP_PAD_SMALL")
      (description "Test Point")
      (libsource (lib "Symbols") (part "TESTPOINT_PAD_SMALL"))
    )
    (comp (ref "U9")
      (value "ADS62P48IRGCT")
      (footprint "ADC_ADS62P48IRGCT")
      (description "ADC - 14 BIT 210MSPS SUAL - VQFN-64")
      (fields
        (field (name "VOLTAGE") "3.15 V ~ 3.6 V / 1.7 V ~ 1.9 V")
        (field (name "MFG") "Texas Instruments")
        (field (name "CREATEDBY") "Jonathan Bouchard")
      )
      (libsource (lib "S7CAS_LIB2023") (part "ADC_ADS62P48IRGCT"))
    )
    (comp (ref "U10")
      (value "ADA4927-2YCPZ-R2")
      (footprint "OPAMP_ADA4927-2YCPZ-R2")
      (description "OPAMP - CFA 2.3GHZ - QFN-24")
      (fields
        (field (name "VOLTAGE") "4.5 V ~ 11 V, ±2.25 V ~ 5.5 V")
        (field (name "MFG") "Analog Devices")
        (field (name "CREATEDBY") "Jonathan Bouchard")
      )
      (libsource (lib "S7CAS_LIB2023") (part "OPAMP_ADA4927-2YCPZ-R2"))
    )
  )
  (nets
    (net (code "4") (name "+1V8D") (class "Default")
      (node (ref "C270") (pin "1") (pinfunction "1_1") (pintype "passive"))
      (node (ref "C271") (pin "1") (pinfunction "1_1") (pintype "passive"))
      (node (ref "C272") (pin "1") (pinfunction "1_1") (pintype "passive"))
      (node (ref "C273") (pin "1") (pinfunction "1_1") (pintype "passive"))
      (node (ref "C274") (pin "1") (pinfunction "1_1") (pintype "passive"))
      (node (ref "C275") (pin "1") (pinfunction "1_1") (pintype "passive"))
      (node (ref "C276") (pin "1") (pinfunction "1_1") (pintype "passive"))
      (node (ref "C277") (pin "1") (pinfunction "1_1") (pintype "passive"))
      (node (ref "C278") (pin "1") (pinfunction "1_1") (pintype "passive"))
      (node (ref "C279") (pin "1") (pinfunction "1_1") (pintype "passive"))
      (node (ref "C280") (pin "1") (pinfunction "1_1") (pintype "passive"))
      (node (ref "C281") (pin "1") (pinfunction "1_1") (pintype "passive"))
      (node (ref "U9") (pin "1") (pinfunction "DRVDD_1") (pintype "passive"))
      (node (ref "U9") (pin "38") (pinfunction "DRVDD_38") (pintype "passive"))
      (node (ref "U9") (pin "48") (pinfunction "DRVDD_48") (pintype "passive"))
      (node (ref "U9") (pin "58") (pinfunction "DRVDD_58") (pintype "passive"))
    )
    (net (code "5") (name "+3V3A") (class "Default")
      (node (ref "C282") (pin "1") (pinfunction "1_1") (pintype "passive"))
      (node (ref "C283") (pin "1") (pinfunction "1_1") (pintype "passive"))
      (node (ref "C284") (pin "1") (pinfunction "1_1") (pintype "passive"))
      (node (ref "C285") (pin "1") (pinfunction "1_1") (pintype "passive"))
      (node (ref "C286") (pin "1") (pinfunction "1_1") (pintype "passive"))
      (node (ref "C287") (pin "1") (pinfunction "1_1") (pintype "passive"))
      (node (ref "C288") (pin "1") (pinfunction "1_1") (pintype "passive"))
      (node (ref "C289") (pin "1") (pinfunction "1_1") (pintype "passive"))
      (node (ref "C290") (pin "1") (pinfunction "1_1") (pintype "passive"))
      (node (ref "U9") (pin "16") (pinfunction "AVDD_16") (pintype "passive"))
      (node (ref "U9") (pin "33") (pinfunction "AVDD_33") (pintype "passive"))
      (node (ref "U9") (pin "34") (pinfunction "AVDD_34") (pintype "passive"))
    )
    (net (code "6") (name "+5V0A") (class "Default")
      (node (ref "C240") (pin "1") (pinfunction "1_1") (pintype "passive"))
      (node (ref "C241") (pin "1") (pinfunction "1_1") (pintype "passive"))
      (node (ref "C242") (pin "1") (pinfunction "1_1") (pintype "passive"))
      (node (ref "C243") (pin "1") (pinfunction "1_1") (pintype "passive"))
      (node (ref "C244") (pin "1") (pinfunction "1_1") (pintype "passive"))
      (node (ref "C245") (pin "1") (pinfunction "1_1") (pintype "passive"))
      (node (ref "C246") (pin "1") (pinfunction "1_1") (pintype "passive"))
      (node (ref "C256") (pin "1") (pinfunction "1_1") (pintype "passive"))
      (node (ref "C257") (pin "1") (pinfunction "1_1") (pintype "passive"))
      (node (ref "C258") (pin "1") (pinfunction "1_1") (pintype "passive"))
      (node (ref "C259") (pin "1") (pinfunction "1_1") (pintype "passive"))
      (node (ref "C260") (pin "1") (pinfunction "1_1") (pintype "passive"))
      (node (ref "C261") (pin "1") (pinfunction "1_1") (pintype "passive"))
      (node (ref "C262") (pin "1") (pinfunction "1_1") (pintype "passive"))
      (node (ref "U10") (pin "10") (pinfunction "+VS2_10") (pintype "passive"))
      (node (ref "U10") (pin "3") (pinfunction "+VS1_3") (pintype "passive"))
      (node (ref "U10") (pin "4") (pinfunction "+VS1_4") (pintype "passive"))
      (node (ref "U10") (pin "9") (pinfunction "+VS2_9") (pintype "passive"))
    )
    (net (code "7") (name "-5V0A") (class "Default")
      (node (ref "C247") (pin "1") (pinfunction "1_1") (pintype "passive"))
      (node (ref "C248") (pin "1") (pinfunction "1_1") (pintype "passive"))
      (node (ref "C249") (pin "1") (pinfunction "1_1") (pintype "passive"))
      (node (ref "C250") (pin "1") (pinfunction "1_1") (pintype "passive"))
      (node (ref "C251") (pin "1") (pinfunction "1_1") (pintype "passive"))
      (node (ref "C252") (pin "1") (pinfunction "1_1") (pintype "passive"))
      (node (ref "C253") (pin "1") (pinfunction "1_1") (pintype "passive"))
      (node (ref "C263") (pin "1") (pinfunction "1_1") (pintype "passive"))
      (node (ref "C264") (pin "1") (pinfunction "1_1") (pintype "passive"))
      (node (ref "C265") (pin "1") (pinfunction "1_1") (pintype "passive"))
      (node (ref "C266") (pin "1") (pinfunction "1_1") (pintype "passive"))
      (node (ref "C267") (pin "1") (pinfunction "1_1") (pintype "passive"))
      (node (ref "C268") (pin "1") (pinfunction "1_1") (pintype "passive"))
      (node (ref "C269") (pin "1") (pinfunction "1_1") (pintype "passive"))
      (node (ref "U10") (pin "15") (pinfunction "-VS2_15") (pintype "passive"))
      (node (ref "U10") (pin "16") (pinfunction "-VS2_16") (pintype "passive"))
      (node (ref "U10") (pin "21") (pinfunction "-VS1_21") (pintype "passive"))
      (node (ref "U10") (pin "22") (pinfunction "-VS1_22") (pintype "passive"))
    )
    (net (code "8") (name "/ADC_CM") (class "Default")
      (node (ref "C237") (pin "1") (pinfunction "1_1") (pintype "passive"))
      (node (ref "TP47") (pin "1") (pinfunction "A_1") (pintype "passive"))
      (node (ref "U10") (pin "11") (pinfunction "VOCM2_11") (pintype "passive"))
      (node (ref "U10") (pin "17") (pinfunction "VOCM1_17") (pintype "passive"))
      (node (ref "U9") (pin "23") (pinfunction "CM_23") (pintype "passive"))
    )
    (net (code "9") (name "/ADC_CTRL1") (class "Default")
      (node (ref "TP44") (pin "1") (pinfunction "A_1") (pintype "passive"))
      (node (ref "U9") (pin "35") (pinfunction "CTRL1_35") (pintype "passive"))
    )
    (net (code "10") (name "/ADC_CTRL2") (class "Default")
      (node (ref "TP45") (pin "1") (pinfunction "A_1") (pintype "passive"))
      (node (ref "U9") (pin "36") (pinfunction "CTRL2_36") (pintype "passive"))
    )
    (net (code "11") (name "/ADC_CTRL3") (class "Default")
      (node (ref "TP46") (pin "1") (pinfunction "A_1") (pintype "passive"))
      (node (ref "U9") (pin "37") (pinfunction "CTRL3_37") (pintype "passive"))
    )
    (net (code "12") (name "/ADC_SCLK") (class "Default")
      (node (ref "TP40") (pin "1") (pinfunction "A_1") (pintype "passive"))
      (node (ref "U9") (pin "13") (pinfunction "SCLK_13") (pintype "passive"))
    )
    (net (code "13") (name "/CLK_ADC_400MHZ_N") (class "Default")
      (node (ref "C236") (pin "1") (pinfunction "1_1") (pintype "passive"))
      (node (ref "R94") (pin "1") (pinfunction "1_1") (pintype "passive"))
    )
    (net (code "14") (name "/CLK_ADC_400MHZ_P") (class "Default")
      (node (ref "C235") (pin "1") (pinfunction "1_1") (pintype "passive"))
      (node (ref "R95") (pin "1") (pinfunction "1_1") (pintype "passive"))
    )
    (net (code "15") (name "/CLK_ADC_OUT_N") (class "Default")
      (node (ref "TP39") (pin "1") (pinfunction "A_1") (pintype "passive"))
      (node (ref "U9") (pin "56") (pinfunction "CLKOUTM_56") (pintype "passive"))
    )
    (net (code "16") (name "/CLK_ADC_OUT_P") (class "Default")
      (node (ref "TP37") (pin "1") (pinfunction "A_1") (pintype "passive"))
      (node (ref "U9") (pin "57") (pinfunction "CLKOUTP_57") (pintype "passive"))
    )
    (net (code "17") (name "/DA0_N") (class "Default")
      (node (ref "U9") (pin "40") (pinfunction "DA0M_40") (pintype "output"))
    )
    (net (code "18") (name "/DA0_P") (class "Default")
      (node (ref "U9") (pin "41") (pinfunction "DA0P_41") (pintype "output"))
    )
    (net (code "19") (name "/DA2_N") (class "Default")
      (node (ref "U9") (pin "42") (pinfunction "DA2M_42") (pintype "output"))
    )
    (net (code "20") (name "/DA2_P") (class "Default")
      (node (ref "U9") (pin "43") (pinfunction "DA2P_43") (pintype "output"))
    )
    (net (code "21") (name "/DA4_N") (class "Default")
      (node (ref "U9") (pin "44") (pinfunction "DA4M_44") (pintype "output"))
    )
    (net (code "22") (name "/DA4_P") (class "Default")
      (node (ref "U9") (pin "45") (pinfunction "DA4P_45") (pintype "output"))
    )
    (net (code "23") (name "/DA6_N") (class "Default")
      (node (ref "U9") (pin "46") (pinfunction "DA6M_46") (pintype "output"))
    )
    (net (code "24") (name "/DA6_P") (class "Default")
      (node (ref "U9") (pin "47") (pinfunction "DA6P_47") (pintype "output"))
    )
    (net (code "25") (name "/DA8_N") (class "Default")
      (node (ref "U9") (pin "50") (pinfunction "DA8M_50") (pintype "output"))
    )
    (net (code "26") (name "/DA8_P") (class "Default")
      (node (ref "U9") (pin "51") (pinfunction "DA8P_51") (pintype "output"))
    )
    (net (code "27") (name "/DA10_N") (class "Default")
      (node (ref "U9") (pin "52") (pinfunction "DA10M_52") (pintype "output"))
    )
    (net (code "28") (name "/DA10_P") (class "Default")
      (node (ref "U9") (pin "53") (pinfunction "DA10P_53") (pintype "output"))
    )
    (net (code "29") (name "/DA12_N") (class "Default")
      (node (ref "U9") (pin "54") (pinfunction "DA12M_54") (pintype "output"))
    )
    (net (code "30") (name "/DA12_P") (class "Default")
      (node (ref "U9") (pin "55") (pinfunction "DA12P_55") (pintype "output"))
    )
    (net (code "31") (name "/DB0_N") (class "Default")
      (node (ref "U9") (pin "60") (pinfunction "DB0M_60") (pintype "output"))
    )
    (net (code "32") (name "/DB0_P") (class "Default")
      (node (ref "U9") (pin "61") (pinfunction "DB0P_61") (pintype "output"))
    )
    (net (code "33") (name "/DB2_N") (class "Default")
      (node (ref "U9") (pin "62") (pinfunction "DB2M_62") (pintype "output"))
    )
    (net (code "34") (name "/DB2_P") (class "Default")
      (node (ref "U9") (pin "63") (pinfunction "DB2P_63") (pintype "output"))
    )
    (net (code "35") (name "/DB4_N") (class "Default")
      (node (ref "U9") (pin "2") (pinfunction "DB4M_2") (pintype "output"))
    )
    (net (code "36") (name "/DB4_P") (class "Default")
      (node (ref "U9") (pin "3") (pinfunction "DB4P_3") (pintype "output"))
    )
    (net (code "37") (name "/DB6_N") (class "Default")
      (node (ref "U9") (pin "4") (pinfunction "DB6M_4") (pintype "output"))
    )
    (net (code "38") (name "/DB6_P") (class "Default")
      (node (ref "U9") (pin "5") (pinfunction "DB6P_5") (pintype "output"))
    )
    (net (code "39") (name "/DB8_N") (class "Default")
      (node (ref "U9") (pin "6") (pinfunction "DB8M_6") (pintype "output"))
    )
    (net (code "40") (name "/DB8_P") (class "Default")
      (node (ref "U9") (pin "7") (pinfunction "DB8P_7") (pintype "output"))
    )
    (net (code "41") (name "/DB10_N") (class "Default")
      (node (ref "U9") (pin "8") (pinfunction "DB10M_8") (pintype "output"))
    )
    (net (code "42") (name "/DB10_P") (class "Default")
      (node (ref "U9") (pin "9") (pinfunction "DB10P_9") (pintype "output"))
    )
    (net (code "43") (name "/DB12_N") (class "Default")
      (node (ref "U9") (pin "10") (pinfunction "DB12M_10") (pintype "output"))
    )
    (net (code "44") (name "/DB12_P") (class "Default")
      (node (ref "U9") (pin "11") (pinfunction "DB12P_11") (pintype "output"))
    )
    (net (code "45") (name "/MISO") (class "Default")
      (node (ref "TP43") (pin "1") (pinfunction "A_1") (pintype "passive"))
      (node (ref "U9") (pin "64") (pinfunction "SDOUT_64") (pintype "passive"))
    )
    (net (code "46") (name "/MOSI") (class "Default")
      (node (ref "TP42") (pin "1") (pinfunction "A_1") (pintype "passive"))
      (node (ref "U9") (pin "14") (pinfunction "SDATA_14") (pintype "passive"))
    )
    (net (code "47") (name "/PD2") (class "Default")
      (node (ref "U10") (pin "14") (pinfunction "~{PD}2_14") (pintype "passive"))
      (node (ref "U10") (pin "20") (pinfunction "~{PD}1_20") (pintype "passive"))
    )
    (net (code "48") (name "/RESET") (class "Default")
      (node (ref "TP38") (pin "1") (pinfunction "A_1") (pintype "passive"))
      (node (ref "U9") (pin "12") (pinfunction "RESET_12") (pintype "passive"))
    )
    (net (code "49") (name "/SEN") (class "Default")
      (node (ref "TP41") (pin "1") (pinfunction "A_1") (pintype "passive"))
      (node (ref "U9") (pin "15") (pinfunction "SEN_15") (pintype "passive"))
    )
    (net (code "50") (name "/SMA_IN1") (class "Default")
      (node (ref "D6") (pin "1") (pinfunction "i/o_1") (pintype "passive"))
      (node (ref "J7") (pin "1") (pinfunction "1_1") (pintype "passive"))
      (node (ref "R101") (pin "1") (pinfunction "1_1") (pintype "passive"))
      (node (ref "R99") (pin "1") (pinfunction "1_1") (pintype "passive"))
      (node (ref "TP49") (pin "1") (pinfunction "A_1") (pintype "passive"))
    )
    (net (code "51") (name "/SMA_IN2") (class "Default")
      (node (ref "D7") (pin "1") (pinfunction "i/o_1") (pintype "passive"))
      (node (ref "J8") (pin "1") (pinfunction "1_1") (pintype "passive"))
      (node (ref "R108") (pin "1") (pinfunction "1_1") (pintype "passive"))
      (node (ref "R110") (pin "1") (pinfunction "1_1") (pintype "passive"))
      (node (ref "TP53") (pin "1") (pinfunction "A_1") (pintype "passive"))
    )
    (net (code "55") (name "GND") (class "Default")
      (node (ref "C237") (pin "2") (pinfunction "2_2") (pintype "passive"))
      (node (ref "C240") (pin "2") (pinfunction "2_2") (pintype "passive"))
      (node (ref "C241") (pin "2") (pinfunction "2_2") (pintype "passive"))
      (node (ref "C242") (pin "2") (pinfunction "2_2") (pintype "passive"))
      (node (ref "C243") (pin "2") (pinfunction "2_2") (pintype "passive"))
      (node (ref "C244") (pin "2") (pinfunction "2_2") (pintype "passive"))
      (node (ref "C245") (pin "2") (pinfunction "2_2") (pintype "passive"))
      (node (ref "C246") (pin "2") (pinfunction "2_2") (pintype "passive"))
      (node (ref "C247") (pin "2") (pinfunction "2_2") (pintype "passive"))
      (node (ref "C248") (pin "2") (pinfunction "2_2") (pintype "passive"))
      (node (ref "C249") (pin "2") (pinfunction "2_2") (pintype "passive"))
      (node (ref "C250") (pin "2") (pinfunction "2_2") (pintype "passive"))
      (node (ref "C251") (pin "2") (pinfunction "2_2") (pintype "passive"))
      (node (ref "C252") (pin "2") (pinfunction "2_2") (pintype "passive"))
      (node (ref "C253") (pin "2") (pinfunction "2_2") (pintype "passive"))
      (node (ref "C256") (pin "2") (pinfunction "2_2") (pintype "passive"))
      (node (ref "C257") (pin "2") (pinfunction "2_2") (pintype "passive"))
      (node (ref "C258") (pin "2") (pinfunction "2_2") (pintype "passive"))
      (node (ref "C259") (pin "2") (pinfunction "2_2") (pintype "passive"))
      (node (ref "C260") (pin "2") (pinfunction "2_2") (pintype "passive"))
      (node (ref "C261") (pin "2") (pinfunction "2_2") (pintype "passive"))
      (node (ref "C262") (pin "2") (pinfunction "2_2") (pintype "passive"))
      (node (ref "C263") (pin "2") (pinfunction "2_2") (pintype "passive"))
      (node (ref "C264") (pin "2") (pinfunction "2_2") (pintype "passive"))
      (node (ref "C265") (pin "2") (pinfunction "2_2") (pintype "passive"))
      (node (ref "C266") (pin "2") (pinfunction "2_2") (pintype "passive"))
      (node (ref "C267") (pin "2") (pinfunction "2_2") (pintype "passive"))
      (node (ref "C268") (pin "2") (pinfunction "2_2") (pintype "passive"))
      (node (ref "C269") (pin "2") (pinfunction "2_2") (pintype "passive"))
      (node (ref "C270") (pin "2") (pinfunction "2_2") (pintype "passive"))
      (node (ref "C271") (pin "2") (pinfunction "2_2") (pintype "passive"))
      (node (ref "C272") (pin "2") (pinfunction "2_2") (pintype "passive"))
      (node (ref "C273") (pin "2") (pinfunction "2_2") (pintype "passive"))
      (node (ref "C274") (pin "2") (pinfunction "2_2") (pintype "passive"))
      (node (ref "C275") (pin "2") (pinfunction "2_2") (pintype "passive"))
      (node (ref "C276") (pin "2") (pinfunction "2_2") (pintype "passive"))
      (node (ref "C277") (pin "2") (pinfunction "2_2") (pintype "passive"))
      (node (ref "C278") (pin "2") (pinfunction "2_2") (pintype "passive"))
      (node (ref "C279") (pin "2") (pinfunction "2_2") (pintype "passive"))
      (node (ref "C280") (pin "2") (pinfunction "2_2") (pintype "passive"))
      (node (ref "C281") (pin "2") (pinfunction "2_2") (pintype "passive"))
      (node (ref "C282") (pin "2") (pinfunction "2_2") (pintype "passive"))
      (node (ref "C283") (pin "2") (pinfunction "2_2") (pintype "passive"))
      (node (ref "C284") (pin "2") (pinfunction "2_2") (pintype "passive"))
      (node (ref "C285") (pin "2") (pinfunction "2_2") (pintype "passive"))
      (node (ref "C286") (pin "2") (pinfunction "2_2") (pintype "passive"))
      (node (ref "C287") (pin "2") (pinfunction "2_2") (pintype "passive"))
      (node (ref "C288") (pin "2") (pinfunction "2_2") (pintype "passive"))
      (node (ref "C289") (pin "2") (pinfunction "2_2") (pintype "passive"))
      (node (ref "C290") (pin "2") (pinfunction "2_2") (pintype "passive"))
      (node (ref "D6") (pin "2") (pinfunction "i/o_2") (pintype "passive"))
      (node (ref "D7") (pin "2") (pinfunction "i/o_2") (pintype "passive"))
      (node (ref "J7") (pin "2") (pinfunction "2_2") (pintype "passive"))
      (node (ref "J7") (pin "3") (pinfunction "3_3") (pintype "passive"))
      (node (ref "J7") (pin "4") (pinfunction "4_4") (pintype "passive"))
      (node (ref "J7") (pin "5") (pinfunction "5_5") (pintype "passive"))
      (node (ref "J8") (pin "2") (pinfunction "2_2") (pintype "passive"))
      (node (ref "J8") (pin "3") (pinfunction "3_3") (pintype "passive"))
      (node (ref "J8") (pin "4") (pinfunction "4_4") (pintype "passive"))
      (node (ref "J8") (pin "5") (pinfunction "5_5") (pintype "passive"))
      (node (ref "R100") (pin "1") (pinfunction "1_1") (pintype "passive"))
      (node (ref "R101") (pin "2") (pinfunction "2_2") (pintype "passive"))
      (node (ref "R109") (pin "1") (pinfunction "1_1") (pintype "passive"))
      (node (ref "R110") (pin "2") (pinfunction "2_2") (pintype "passive"))
      (node (ref "R94") (pin "2") (pinfunction "2_2") (pintype "passive"))
      (node (ref "R95") (pin "2") (pinfunction "2_2") (pintype "passive"))
      (node (ref "TP50") (pin "1") (pinfunction "A_1") (pintype "passive"))
      (node (ref "U10") (pin "PAD") (pinfunction "PAD_PAD") (pintype "power_in"))
      (node (ref "U9") (pin "17") (pinfunction "AGND_17") (pintype "passive"))
      (node (ref "U9") (pin "18") (pinfunction "AGND_18") (pintype "passive"))
      (node (ref "U9") (pin "21") (pinfunction "AGND_21") (pintype "passive"))
      (node (ref "U9") (pin "24") (pinfunction "AGND_24") (pintype "passive"))
      (node (ref "U9") (pin "27") (pinfunction "AGND_27") (pintype "passive"))
      (node (ref "U9") (pin "28") (pinfunction "AGND_28") (pintype "passive"))
      (node (ref "U9") (pin "31") (pinfunction "AGND_31") (pintype "passive"))
      (node (ref "U9") (pin "32") (pinfunction "AGND_32") (pintype "passive"))
      (node (ref "U9") (pin "39") (pinfunction "DRGND_39") (pintype "passive"))
      (node (ref "U9") (pin "49") (pinfunction "DRGND_49") (pintype "passive"))
      (node (ref "U9") (pin "59") (pinfunction "DRGND_59") (pintype "passive"))
      (node (ref "U9") (pin "PAD") (pinfunction "DRGND_PAD") (pintype "passive"))
    )
    (net (code "56") (name "Net-(C238-Pad2)") (class "Default")
      (node (ref "C238") (pin "2") (pinfunction "2_2") (pintype "passive"))
      (node (ref "C239") (pin "1") (pinfunction "1_1") (pintype "passive"))
    )
    (net (code "57") (name "Net-(C254-Pad2)") (class "Default")
      (node (ref "C254") (pin "2") (pinfunction "2_2") (pintype "passive"))
      (node (ref "C255") (pin "1") (pinfunction "1_1") (pintype "passive"))
    )
    (net (code "58") (name "Net-(L5-Pad2)") (class "Default")
      (node (ref "L5") (pin "2") (pinfunction "2_2") (pintype "passive"))
      (node (ref "R96") (pin "1") (pinfunction "1_1") (pintype "passive"))
    )
    (net (code "59") (name "Net-(L6-Pad2)") (class "Default")
      (node (ref "L6") (pin "2") (pinfunction "2_2") (pintype "passive"))
      (node (ref "R102") (pin "1") (pinfunction "1_1") (pintype "passive"))
    )
    (net (code "60") (name "Net-(L7-Pad2)") (class "Default")
      (node (ref "L7") (pin "2") (pinfunction "2_2") (pintype "passive"))
      (node (ref "R107") (pin "1") (pinfunction "1_1") (pintype "passive"))
    )
    (net (code "61") (name "Net-(L8-Pad2)") (class "Default")
      (node (ref "L8") (pin "2") (pinfunction "2_2") (pintype "passive"))
      (node (ref "R113") (pin "1") (pinfunction "1_1") (pintype "passive"))
    )
    (net (code "62") (name "Net-(TP48-A)") (class "Default")
      (node (ref "C238") (pin "1") (pinfunction "1_1") (pintype "passive"))
      (node (ref "R96") (pin "2") (pinfunction "2_2") (pintype "passive"))
      (node (ref "TP48") (pin "1") (pinfunction "A_1") (pintype "passive"))
      (node (ref "U9") (pin "29") (pinfunction "INP_A_29") (pintype "passive"))
    )
    (net (code "63") (name "Net-(TP51-A)") (class "Default")
      (node (ref "C239") (pin "2") (pinfunction "2_2") (pintype "passive"))
      (node (ref "R102") (pin "2") (pinfunction "2_2") (pintype "passive"))
      (node (ref "TP51") (pin "1") (pinfunction "A_1") (pintype "passive"))
      (node (ref "U9") (pin "30") (pinfunction "INM_A_30") (pintype "passive"))
    )
    (net (code "64") (name "Net-(TP52-A)") (class "Default")
      (node (ref "C254") (pin "1") (pinfunction "1_1") (pintype "passive"))
      (node (ref "R107") (pin "2") (pinfunction "2_2") (pintype "passive"))
      (node (ref "TP52") (pin "1") (pinfunction "A_1") (pintype "passive"))
      (node (ref "U9") (pin "19") (pinfunction "INP_B_19") (pintype "passive"))
    )
    (net (code "65") (name "Net-(TP54-A)") (class "Default")
      (node (ref "C255") (pin "2") (pinfunction "2_2") (pintype "passive"))
      (node (ref "R113") (pin "2") (pinfunction "2_2") (pintype "passive"))
      (node (ref "TP54") (pin "1") (pinfunction "A_1") (pintype "passive"))
      (node (ref "U9") (pin "20") (pinfunction "INM_B_20") (pintype "passive"))
    )
    (net (code "66") (name "Net-(U9C-CLKM)") (class "Default")
      (node (ref "C236") (pin "2") (pinfunction "2_2") (pintype "passive"))
      (node (ref "U9") (pin "26") (pinfunction "CLKM_26") (pintype "passive"))
    )
    (net (code "67") (name "Net-(U9C-CLKP)") (class "Default")
      (node (ref "C235") (pin "2") (pinfunction "2_2") (pintype "passive"))
      (node (ref "U9") (pin "25") (pinfunction "CLKP_25") (pintype "passive"))
    )
    (net (code "68") (name "Net-(U10A-+FB1)") (class "Default")
      (node (ref "R103") (pin "2") (pinfunction "2_2") (pintype "passive"))
      (node (ref "R104") (pin "2") (pinfunction "2_2") (pintype "passive"))
      (node (ref "U10") (pin "2") (pinfunction "+FB1_2") (pintype "passive"))
    )
    (net (code "69") (name "Net-(U10A-+IN1)") (class "Default")
      (node (ref "R97") (pin "2") (pinfunction "2_2") (pintype "passive"))
      (node (ref "R98") (pin "2") (pinfunction "2_2") (pintype "passive"))
      (node (ref "R99") (pin "2") (pinfunction "2_2") (pintype "passive"))
      (node (ref "U10") (pin "24") (pinfunction "+IN1_24") (pintype "passive"))
    )
    (net (code "70") (name "Net-(U10A-+OUT1)") (class "Default")
      (node (ref "L6") (pin "1") (pinfunction "1_1") (pintype "passive"))
      (node (ref "U10") (pin "18") (pinfunction "+OUT1_18") (pintype "passive"))
    )
    (net (code "71") (name "Net-(U10A--FB1)") (class "Default")
      (node (ref "R97") (pin "1") (pinfunction "1_1") (pintype "passive"))
      (node (ref "R98") (pin "1") (pinfunction "1_1") (pintype "passive"))
      (node (ref "U10") (pin "23") (pinfunction "-FB1_23") (pintype "passive"))
    )
    (net (code "72") (name "Net-(U10A--IN1)") (class "Default")
      (node (ref "R100") (pin "2") (pinfunction "2_2") (pintype "passive"))
      (node (ref "R103") (pin "1") (pinfunction "1_1") (pintype "passive"))
      (node (ref "R104") (pin "1") (pinfunction "1_1") (pintype "passive"))
      (node (ref "U10") (pin "1") (pinfunction "-IN1_1") (pintype "passive"))
    )
    (net (code "73") (name "Net-(U10A--OUT1)") (class "Default")
      (node (ref "L5") (pin "1") (pinfunction "1_1") (pintype "passive"))
      (node (ref "U10") (pin "19") (pinfunction "-OUT1_19") (pintype "passive"))
    )
    (net (code "74") (name "Net-(U10B-+FB2)") (class "Default")
      (node (ref "R111") (pin "2") (pinfunction "2_2") (pintype "passive"))
      (node (ref "R112") (pin "2") (pinfunction "2_2") (pintype "passive"))
      (node (ref "U10") (pin "8") (pinfunction "+FB2_8") (pintype "passive"))
    )
    (net (code "75") (name "Net-(U10B-+IN2)") (class "Default")
      (node (ref "R105") (pin "2") (pinfunction "2_2") (pintype "passive"))
      (node (ref "R106") (pin "2") (pinfunction "2_2") (pintype "passive"))
      (node (ref "R108") (pin "2") (pinfunction "2_2") (pintype "passive"))
      (node (ref "U10") (pin "6") (pinfunction "+IN2_6") (pintype "passive"))
    )
    (net (code "76") (name "Net-(U10B-+OUT2)") (class "Default")
      (node (ref "L8") (pin "1") (pinfunction "1_1") (pintype "passive"))
      (node (ref "U10") (pin "12") (pinfunction "+OUT2_12") (pintype "passive"))
    )
    (net (code "77") (name "Net-(U10B--FB2)") (class "Default")
      (node (ref "R105") (pin "1") (pinfunction "1_1") (pintype "passive"))
      (node (ref "R106") (pin "1") (pinfunction "1_1") (pintype "passive"))
      (node (ref "U10") (pin "5") (pinfunction "-FB2_5") (pintype "passive"))
    )
    (net (code "78") (name "Net-(U10B--IN2)") (class "Default")
      (node (ref "R109") (pin "2") (pinfunction "2_2") (pintype "passive"))
      (node (ref "R111") (pin "1") (pinfunction "1_1") (pintype "passive"))
      (node (ref "R112") (pin "1") (pinfunction "1_1") (pintype "passive"))
      (node (ref "U10") (pin "7") (pinfunction "-IN2_7") (pintype "passive"))
    )
    (net (code "79") (name "Net-(U10B--OUT2)") (class "Default")
      (node (ref "L7") (pin "1") (pinfunction "1_1") (pintype "passive"))
      (node (ref "U10") (pin "13") (pinfunction "-OUT2_13") (pintype "passive"))
    )
    (net (code "80") (name "unconnected-(U9C-NC-Pad22)") (class "Default")
      (node (ref "U9") (pin "22") (pinfunction "NC_22") (pintype "passive+no_connect"))
    )
  )
)
